# FPC_KEY.net
KiCad netlist of a schematic drawn in Altium Designer
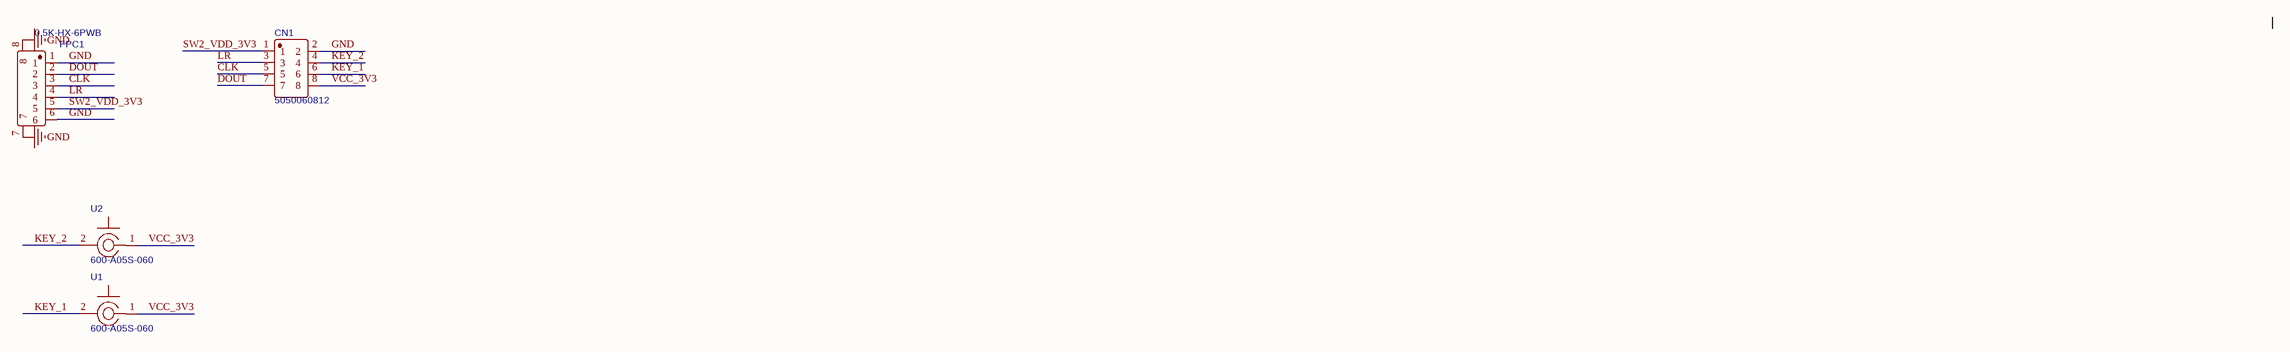
[diagram p0: FPC_KEY.SchDoc]

(export (version "E")
  (design (tool "Eeschema 10.0.6"))
  (components
    (comp (ref "CN1")
      (value "5050060812")
      (footprint "smart bracelet:CONN-SMD_5050060810")
      (fields (field (name "MANUFACTURER") "MOLEX") (field (name "CONTRIBUTOR") "lcsc"))
      (libsource (lib "smart bracelet") (part "5050060812_8pin_DP"))
    )
    (comp (ref "FPC1")
      (value "0.5K-HX-6PWB")
      (footprint "smart bracelet:FPC-SMD_6P-P0.50_HDGC_0.5K-HX-6PWB")
      (fields (field (name "MANUFACTURER") "HDGC(华德共创)") (field (name "CONTRIBUTOR") "LCSC"))
      (libsource (lib "smart bracelet") (part "0.5K-HX-6PWB"))
    )
    (comp (ref "U1")
      (value "600-A05S-060")
      (footprint "smart bracelet:SW-SMD_BD2.50-600-A05S-060")
      (fields (field (name "MANUFACTURER") "HYP(鸿源精密)") (field (name "CONTRIBUTOR") "lcsc"))
      (libsource (lib "smart bracelet") (part "600-A05S-060"))
    )
    (comp (ref "U2")
      (value "600-A05S-060")
      (footprint "smart bracelet:SW-SMD_BD2.50-600-A05S-060")
      (fields (field (name "MANUFACTURER") "HYP(鸿源精密)") (field (name "CONTRIBUTOR") "lcsc"))
      (libsource (lib "smart bracelet") (part "600-A05S-060"))
    )
  )
  (nets
    (net (code "1") (name "/CLK") (class "Default")
      (node (ref "CN1") (pin "5") (pinfunction "5_5") (pintype "passive"))
      (node (ref "FPC1") (pin "3") (pinfunction "3_3") (pintype "passive"))
    )
    (net (code "2") (name "/DOUT") (class "Default")
      (node (ref "CN1") (pin "7") (pinfunction "7_7") (pintype "passive"))
      (node (ref "FPC1") (pin "2") (pinfunction "2_2") (pintype "passive"))
    )
    (net (code "3") (name "/KEY_1") (class "Default")
      (node (ref "CN1") (pin "6") (pinfunction "6_6") (pintype "passive"))
      (node (ref "U1") (pin "2") (pinfunction "2_2") (pintype "passive"))
    )
    (net (code "4") (name "/KEY_2") (class "Default")
      (node (ref "CN1") (pin "4") (pinfunction "4_4") (pintype "passive"))
      (node (ref "U2") (pin "2") (pinfunction "2_2") (pintype "passive"))
    )
    (net (code "5") (name "/LR") (class "Default")
      (node (ref "CN1") (pin "3") (pinfunction "3_3") (pintype "passive"))
      (node (ref "FPC1") (pin "4") (pinfunction "4_4") (pintype "passive"))
    )
    (net (code "6") (name "/SW2_VDD_3V3") (class "Default")
      (node (ref "CN1") (pin "1") (pinfunction "1_1") (pintype "passive"))
      (node (ref "FPC1") (pin "5") (pinfunction "5_5") (pintype "passive"))
    )
    (net (code "7") (name "/VCC_3V3") (class "Default")
      (node (ref "CN1") (pin "8") (pinfunction "8_8") (pintype "passive"))
      (node (ref "U1") (pin "1") (pinfunction "1_1") (pintype "passive"))
      (node (ref "U2") (pin "1") (pinfunction "1_1") (pintype "passive"))
    )
    (net (code "8") (name "GND") (class "Default")
      (node (ref "CN1") (pin "2") (pinfunction "2_2") (pintype "passive"))
      (node (ref "FPC1") (pin "1") (pinfunction "1_1") (pintype "passive"))
      (node (ref "FPC1") (pin "6") (pinfunction "6_6") (pintype "passive"))
      (node (ref "FPC1") (pin "7") (pinfunction "7_7") (pintype "passive"))
      (node (ref "FPC1") (pin "8") (pinfunction "8_8") (pintype "passive"))
    )
  )
)
